# Communication_Part2.net
KiCad netlist of a schematic drawn in Altium Designer
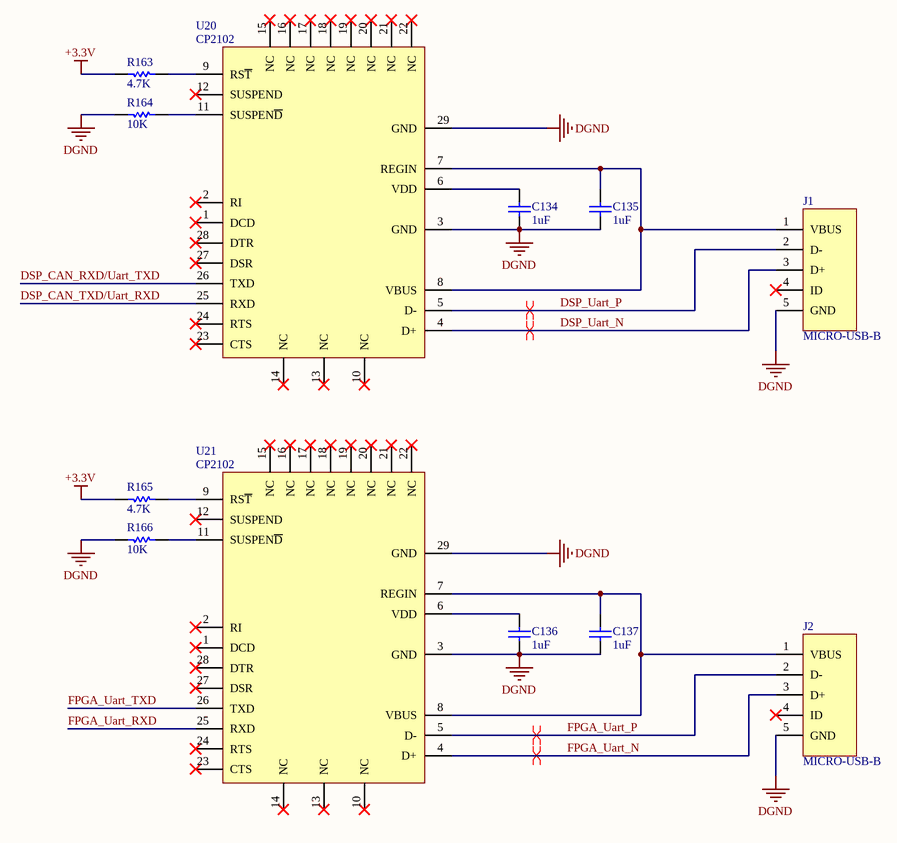
[diagram p0: Communication_Part2.SchDoc]

(export (version "E")
  (design (tool "Eeschema 10.0.6"))
  (components
    (comp (ref "C134")
      (value "1uF")
      (footprint "1608[0603]")
      (description "Capacitor")
      (fields (field (name "Comment") "Cap") (field (name "PUBLISHER") "Altium Limited"))
      (libsource (lib "Miscellaneous Devices") (part "Cap"))
    )
    (comp (ref "C135")
      (value "1uF")
      (footprint "1608[0603]")
      (description "Capacitor")
      (fields (field (name "Comment") "Cap") (field (name "PUBLISHER") "Altium Limited"))
      (libsource (lib "Miscellaneous Devices") (part "Cap"))
    )
    (comp (ref "C136")
      (value "1uF")
      (footprint "1608[0603]")
      (description "Capacitor")
      (fields (field (name "Comment") "Cap") (field (name "PUBLISHER") "Altium Limited"))
      (libsource (lib "Miscellaneous Devices") (part "Cap"))
    )
    (comp (ref "C137")
      (value "1uF")
      (footprint "1608[0603]")
      (description "Capacitor")
      (fields (field (name "Comment") "Cap") (field (name "PUBLISHER") "Altium Limited"))
      (libsource (lib "Miscellaneous Devices") (part "Cap"))
    )
    (comp (ref "J1")
      (value "MICRO-USB-B")
      (footprint "MICRO-USB-B")
      (libsource (lib "DSP_FPGA") (part "MICRO-USB-B"))
    )
    (comp (ref "J2")
      (value "MICRO-USB-B")
      (footprint "MICRO-USB-B")
      (libsource (lib "DSP_FPGA") (part "MICRO-USB-B"))
    )
    (comp (ref "R163")
      (value "4.7K")
      (footprint "1608[0603]")
      (description "Resistor")
      (fields (field (name "Comment") "Res1") (field (name "PUBLISHER") "Altium Limited"))
      (libsource (lib "Miscellaneous Devices") (part "Res1"))
    )
    (comp (ref "R164")
      (value "10K")
      (footprint "1608[0603]")
      (description "Resistor")
      (fields (field (name "Comment") "Res1") (field (name "PUBLISHER") "Altium Limited"))
      (libsource (lib "Miscellaneous Devices") (part "Res1"))
    )
    (comp (ref "R165")
      (value "4.7K")
      (footprint "1608[0603]")
      (description "Resistor")
      (fields (field (name "Comment") "Res1") (field (name "PUBLISHER") "Altium Limited"))
      (libsource (lib "Miscellaneous Devices") (part "Res1"))
    )
    (comp (ref "R166")
      (value "10K")
      (footprint "1608[0603]")
      (description "Resistor")
      (fields (field (name "Comment") "Res1") (field (name "PUBLISHER") "Altium Limited"))
      (libsource (lib "Miscellaneous Devices") (part "Res1"))
    )
    (comp (ref "U20")
      (value "CP2102")
      (footprint "CP2102_QFN28")
      (libsource (lib "DSP_FPGA_Lib") (part "CP2102"))
    )
    (comp (ref "U21")
      (value "CP2102")
      (footprint "CP2102_QFN28")
      (libsource (lib "DSP_FPGA_Lib") (part "CP2102"))
    )
  )
  (nets
    (net (code "1") (name "+3.3V") (class "Default")
      (node (ref "R163") (pin "1") (pinfunction "1_1") (pintype "passive"))
      (node (ref "R165") (pin "1") (pinfunction "1_1") (pintype "passive"))
    )
    (net (code "2") (name "/DSP_CAN_RXD{slash}Uart_TXD") (class "Default")
      (node (ref "U20") (pin "26") (pinfunction "TXD_26") (pintype "passive"))
    )
    (net (code "3") (name "/DSP_CAN_TXD{slash}Uart_RXD") (class "Default")
      (node (ref "U20") (pin "25") (pinfunction "RXD_25") (pintype "passive"))
    )
    (net (code "4") (name "/DSP_Uart_N") (class "Default")
      (node (ref "J1") (pin "3") (pinfunction "D+_3") (pintype "passive"))
      (node (ref "U20") (pin "4") (pinfunction "D+_4") (pintype "passive"))
    )
    (net (code "5") (name "/DSP_Uart_P") (class "Default")
      (node (ref "J1") (pin "2") (pinfunction "D-_2") (pintype "passive"))
      (node (ref "U20") (pin "5") (pinfunction "D-_5") (pintype "passive"))
    )
    (net (code "6") (name "/FPGA_Uart_N") (class "Default")
      (node (ref "J2") (pin "3") (pinfunction "D+_3") (pintype "passive"))
      (node (ref "U21") (pin "4") (pinfunction "D+_4") (pintype "passive"))
    )
    (net (code "7") (name "/FPGA_Uart_P") (class "Default")
      (node (ref "J2") (pin "2") (pinfunction "D-_2") (pintype "passive"))
      (node (ref "U21") (pin "5") (pinfunction "D-_5") (pintype "passive"))
    )
    (net (code "8") (name "/FPGA_Uart_RXD") (class "Default")
      (node (ref "U21") (pin "25") (pinfunction "RXD_25") (pintype "passive"))
    )
    (net (code "9") (name "/FPGA_Uart_TXD") (class "Default")
      (node (ref "U21") (pin "26") (pinfunction "TXD_26") (pintype "passive"))
    )
    (net (code "10") (name "DGND") (class "Default")
      (node (ref "C134") (pin "2") (pinfunction "2_2") (pintype "passive"))
      (node (ref "C135") (pin "2") (pinfunction "2_2") (pintype "passive"))
      (node (ref "C136") (pin "2") (pinfunction "2_2") (pintype "passive"))
      (node (ref "C137") (pin "2") (pinfunction "2_2") (pintype "passive"))
      (node (ref "J1") (pin "5") (pinfunction "GND_5") (pintype "passive"))
      (node (ref "J2") (pin "5") (pinfunction "GND_5") (pintype "passive"))
      (node (ref "R164") (pin "1") (pinfunction "1_1") (pintype "passive"))
      (node (ref "R166") (pin "1") (pinfunction "1_1") (pintype "passive"))
      (node (ref "U20") (pin "29") (pinfunction "GND_29") (pintype "passive"))
      (node (ref "U20") (pin "3") (pinfunction "GND_3") (pintype "passive"))
      (node (ref "U21") (pin "29") (pinfunction "GND_29") (pintype "passive"))
      (node (ref "U21") (pin "3") (pinfunction "GND_3") (pintype "passive"))
    )
    (net (code "11") (name "Net-(J1-VBUS)") (class "Default")
      (node (ref "C135") (pin "1") (pinfunction "1_1") (pintype "passive"))
      (node (ref "J1") (pin "1") (pinfunction "VBUS_1") (pintype "passive"))
      (node (ref "U20") (pin "7") (pinfunction "REGIN_7") (pintype "passive"))
      (node (ref "U20") (pin "8") (pinfunction "VBUS_8") (pintype "passive"))
    )
    (net (code "12") (name "Net-(J2-VBUS)") (class "Default")
      (node (ref "C137") (pin "1") (pinfunction "1_1") (pintype "passive"))
      (node (ref "J2") (pin "1") (pinfunction "VBUS_1") (pintype "passive"))
      (node (ref "U21") (pin "7") (pinfunction "REGIN_7") (pintype "passive"))
      (node (ref "U21") (pin "8") (pinfunction "VBUS_8") (pintype "passive"))
    )
    (net (code "13") (name "Net-(U20-RS~{T})") (class "Default")
      (node (ref "R163") (pin "2") (pinfunction "2_2") (pintype "passive"))
      (node (ref "U20") (pin "9") (pinfunction "RS~{T}_9") (pintype "passive"))
    )
    (net (code "14") (name "Net-(U20-SUSPEN~{D})") (class "Default")
      (node (ref "R164") (pin "2") (pinfunction "2_2") (pintype "passive"))
      (node (ref "U20") (pin "11") (pinfunction "SUSPEN~{D}_11") (pintype "passive"))
    )
    (net (code "15") (name "Net-(U20-VDD)") (class "Default")
      (node (ref "C134") (pin "1") (pinfunction "1_1") (pintype "passive"))
      (node (ref "U20") (pin "6") (pinfunction "VDD_6") (pintype "passive"))
    )
    (net (code "16") (name "Net-(U21-RS~{T})") (class "Default")
      (node (ref "R165") (pin "2") (pinfunction "2_2") (pintype "passive"))
      (node (ref "U21") (pin "9") (pinfunction "RS~{T}_9") (pintype "passive"))
    )
    (net (code "17") (name "Net-(U21-SUSPEN~{D})") (class "Default")
      (node (ref "R166") (pin "2") (pinfunction "2_2") (pintype "passive"))
      (node (ref "U21") (pin "11") (pinfunction "SUSPEN~{D}_11") (pintype "passive"))
    )
    (net (code "18") (name "Net-(U21-VDD)") (class "Default")
      (node (ref "C136") (pin "1") (pinfunction "1_1") (pintype "passive"))
      (node (ref "U21") (pin "6") (pinfunction "VDD_6") (pintype "passive"))
    )
    (net (code "19") (name "unconnected-(J1-ID-Pad4)") (class "Default")
      (node (ref "J1") (pin "4") (pinfunction "ID_4") (pintype "passive+no_connect"))
    )
    (net (code "20") (name "unconnected-(J2-ID-Pad4)") (class "Default")
      (node (ref "J2") (pin "4") (pinfunction "ID_4") (pintype "passive+no_connect"))
    )
    (net (code "21") (name "unconnected-(U20-CTS-Pad23)") (class "Default")
      (node (ref "U20") (pin "23") (pinfunction "CTS_23") (pintype "passive+no_connect"))
    )
    (net (code "22") (name "unconnected-(U20-DCD-Pad1)") (class "Default")
      (node (ref "U20") (pin "1") (pinfunction "DCD_1") (pintype "passive+no_connect"))
    )
    (net (code "23") (name "unconnected-(U20-DSR-Pad27)") (class "Default")
      (node (ref "U20") (pin "27") (pinfunction "DSR_27") (pintype "passive+no_connect"))
    )
    (net (code "24") (name "unconnected-(U20-DTR-Pad28)") (class "Default")
      (node (ref "U20") (pin "28") (pinfunction "DTR_28") (pintype "passive+no_connect"))
    )
    (net (code "25") (name "unconnected-(U20-NC-Pad10)") (class "Default")
      (node (ref "U20") (pin "10") (pinfunction "NC_10") (pintype "passive+no_connect"))
    )
    (net (code "26") (name "unconnected-(U20-NC-Pad13)") (class "Default")
      (node (ref "U20") (pin "13") (pinfunction "NC_13") (pintype "passive+no_connect"))
    )
    (net (code "27") (name "unconnected-(U20-NC-Pad14)") (class "Default")
      (node (ref "U20") (pin "14") (pinfunction "NC_14") (pintype "passive+no_connect"))
    )
    (net (code "28") (name "unconnected-(U20-NC-Pad15)") (class "Default")
      (node (ref "U20") (pin "15") (pinfunction "NC_15") (pintype "passive+no_connect"))
    )
    (net (code "29") (name "unconnected-(U20-NC-Pad16)") (class "Default")
      (node (ref "U20") (pin "16") (pinfunction "NC_16") (pintype "passive+no_connect"))
    )
    (net (code "30") (name "unconnected-(U20-NC-Pad17)") (class "Default")
      (node (ref "U20") (pin "17") (pinfunction "NC_17") (pintype "passive+no_connect"))
    )
    (net (code "31") (name "unconnected-(U20-NC-Pad18)") (class "Default")
      (node (ref "U20") (pin "18") (pinfunction "NC_18") (pintype "passive+no_connect"))
    )
    (net (code "32") (name "unconnected-(U20-NC-Pad19)") (class "Default")
      (node (ref "U20") (pin "19") (pinfunction "NC_19") (pintype "passive+no_connect"))
    )
    (net (code "33") (name "unconnected-(U20-NC-Pad20)") (class "Default")
      (node (ref "U20") (pin "20") (pinfunction "NC_20") (pintype "passive+no_connect"))
    )
    (net (code "34") (name "unconnected-(U20-NC-Pad21)") (class "Default")
      (node (ref "U20") (pin "21") (pinfunction "NC_21") (pintype "passive+no_connect"))
    )
    (net (code "35") (name "unconnected-(U20-NC-Pad22)") (class "Default")
      (node (ref "U20") (pin "22") (pinfunction "NC_22") (pintype "passive+no_connect"))
    )
    (net (code "36") (name "unconnected-(U20-RI-Pad2)") (class "Default")
      (node (ref "U20") (pin "2") (pinfunction "RI_2") (pintype "passive+no_connect"))
    )
    (net (code "37") (name "unconnected-(U20-RTS-Pad24)") (class "Default")
      (node (ref "U20") (pin "24") (pinfunction "RTS_24") (pintype "passive+no_connect"))
    )
    (net (code "38") (name "unconnected-(U20-SUSPEND-Pad12)") (class "Default")
      (node (ref "U20") (pin "12") (pinfunction "SUSPEND_12") (pintype "passive+no_connect"))
    )
    (net (code "39") (name "unconnected-(U21-CTS-Pad23)") (class "Default")
      (node (ref "U21") (pin "23") (pinfunction "CTS_23") (pintype "passive+no_connect"))
    )
    (net (code "40") (name "unconnected-(U21-DCD-Pad1)") (class "Default")
      (node (ref "U21") (pin "1") (pinfunction "DCD_1") (pintype "passive+no_connect"))
    )
    (net (code "41") (name "unconnected-(U21-DSR-Pad27)") (class "Default")
      (node (ref "U21") (pin "27") (pinfunction "DSR_27") (pintype "passive+no_connect"))
    )
    (net (code "42") (name "unconnected-(U21-DTR-Pad28)") (class "Default")
      (node (ref "U21") (pin "28") (pinfunction "DTR_28") (pintype "passive+no_connect"))
    )
    (net (code "43") (name "unconnected-(U21-NC-Pad10)") (class "Default")
      (node (ref "U21") (pin "10") (pinfunction "NC_10") (pintype "passive+no_connect"))
    )
    (net (code "44") (name "unconnected-(U21-NC-Pad13)") (class "Default")
      (node (ref "U21") (pin "13") (pinfunction "NC_13") (pintype "passive+no_connect"))
    )
    (net (code "45") (name "unconnected-(U21-NC-Pad14)") (class "Default")
      (node (ref "U21") (pin "14") (pinfunction "NC_14") (pintype "passive+no_connect"))
    )
    (net (code "46") (name "unconnected-(U21-NC-Pad15)") (class "Default")
      (node (ref "U21") (pin "15") (pinfunction "NC_15") (pintype "passive+no_connect"))
    )
    (net (code "47") (name "unconnected-(U21-NC-Pad16)") (class "Default")
      (node (ref "U21") (pin "16") (pinfunction "NC_16") (pintype "passive+no_connect"))
    )
    (net (code "48") (name "unconnected-(U21-NC-Pad17)") (class "Default")
      (node (ref "U21") (pin "17") (pinfunction "NC_17") (pintype "passive+no_connect"))
    )
    (net (code "49") (name "unconnected-(U21-NC-Pad18)") (class "Default")
      (node (ref "U21") (pin "18") (pinfunction "NC_18") (pintype "passive+no_connect"))
    )
    (net (code "50") (name "unconnected-(U21-NC-Pad19)") (class "Default")
      (node (ref "U21") (pin "19") (pinfunction "NC_19") (pintype "passive+no_connect"))
    )
    (net (code "51") (name "unconnected-(U21-NC-Pad20)") (class "Default")
      (node (ref "U21") (pin "20") (pinfunction "NC_20") (pintype "passive+no_connect"))
    )
    (net (code "52") (name "unconnected-(U21-NC-Pad21)") (class "Default")
      (node (ref "U21") (pin "21") (pinfunction "NC_21") (pintype "passive+no_connect"))
    )
    (net (code "53") (name "unconnected-(U21-NC-Pad22)") (class "Default")
      (node (ref "U21") (pin "22") (pinfunction "NC_22") (pintype "passive+no_connect"))
    )
    (net (code "54") (name "unconnected-(U21-RI-Pad2)") (class "Default")
      (node (ref "U21") (pin "2") (pinfunction "RI_2") (pintype "passive+no_connect"))
    )
    (net (code "55") (name "unconnected-(U21-RTS-Pad24)") (class "Default")
      (node (ref "U21") (pin "24") (pinfunction "RTS_24") (pintype "passive+no_connect"))
    )
    (net (code "56") (name "unconnected-(U21-SUSPEND-Pad12)") (class "Default")
      (node (ref "U21") (pin "12") (pinfunction "SUSPEND_12") (pintype "passive+no_connect"))
    )
  )
)
